# maze_hub_1_1.net
KiCad netlist of a schematic drawn in EAGLE
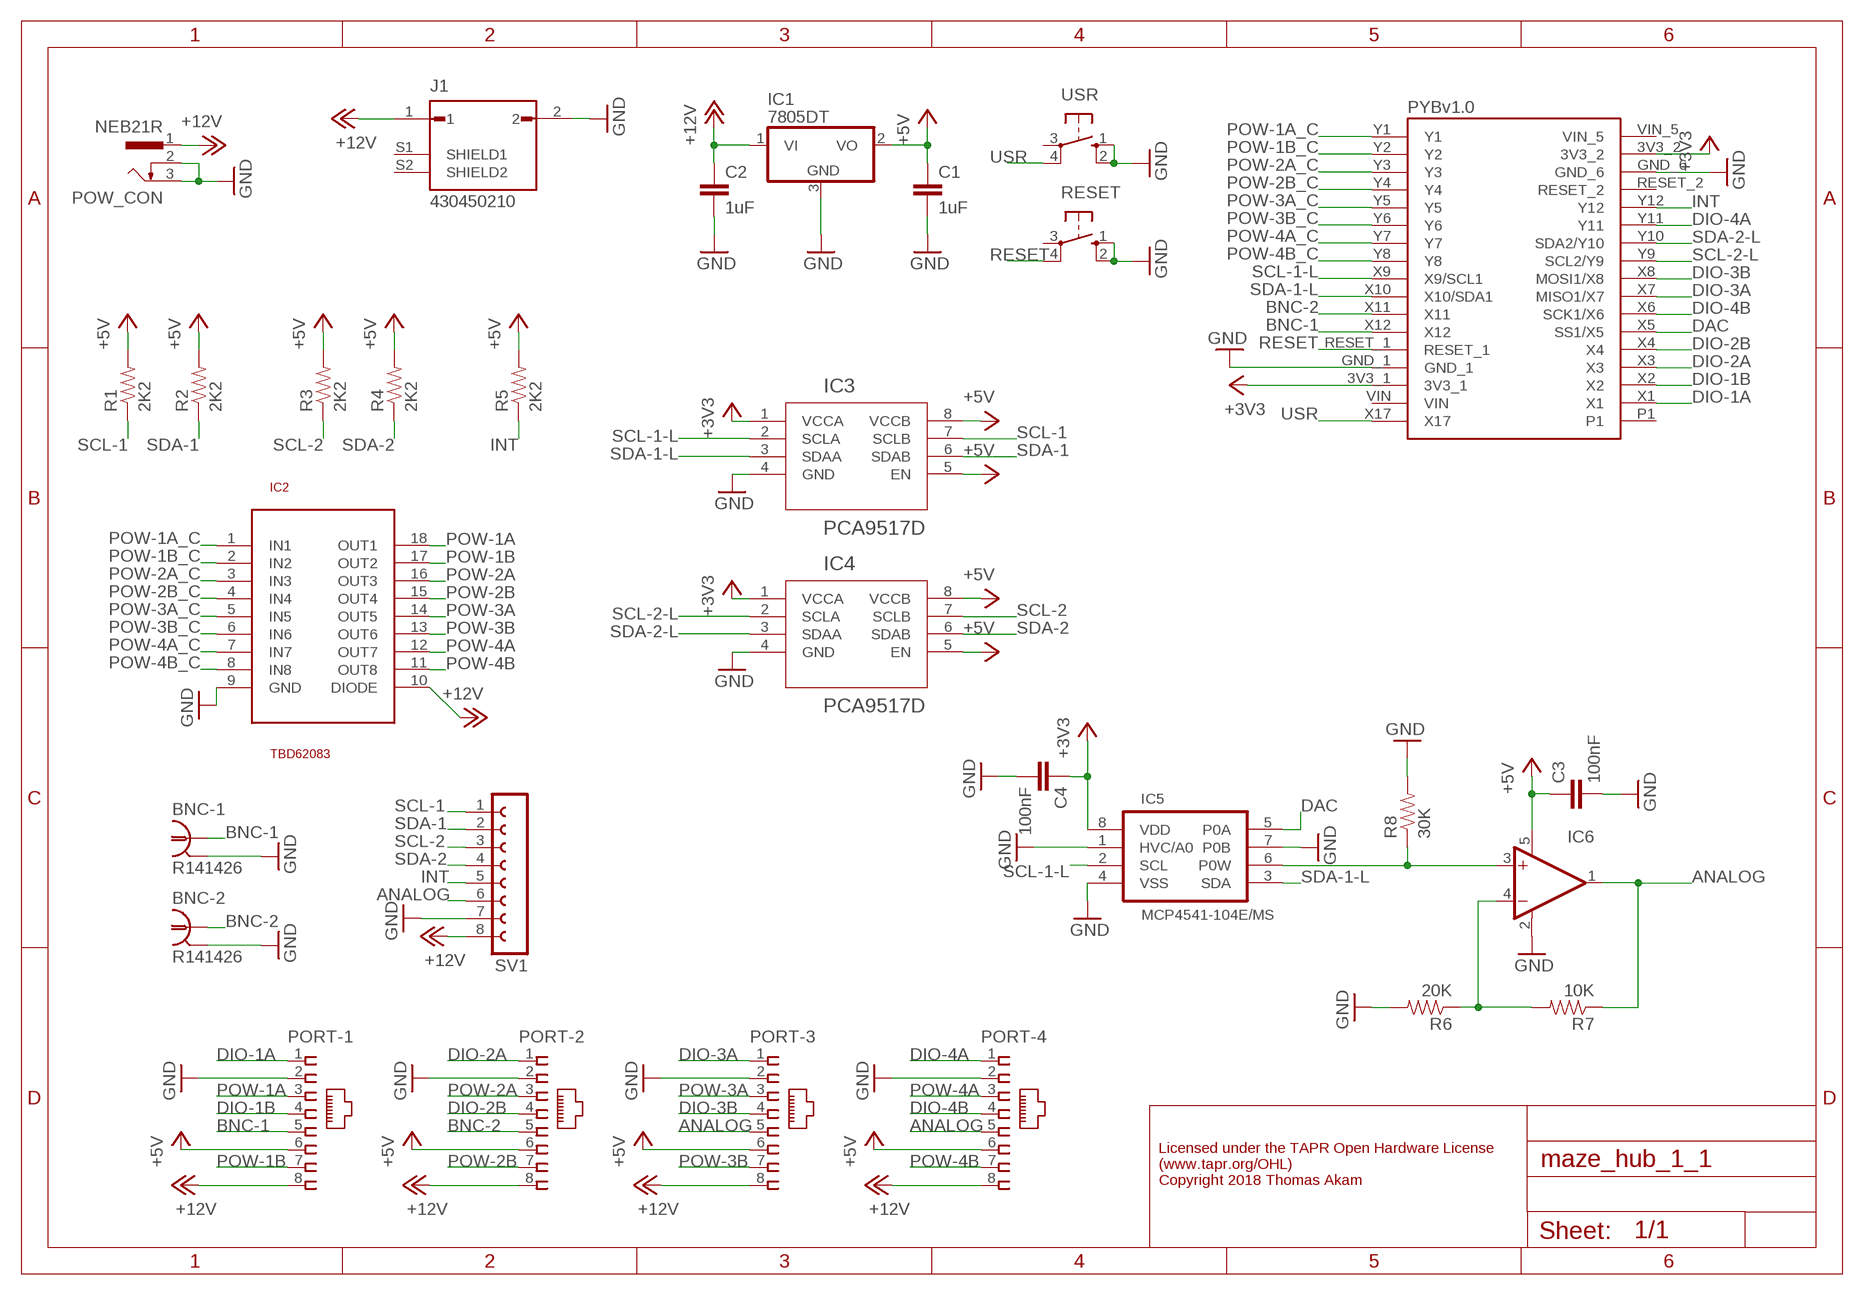
[diagram p0: schematic, sheet 1]

(export (version "E")
  (design (tool "Eeschema 10.0.6"))
  (components
    (comp (ref "BNC-1")
      (value "R141426")
      (footprint "eagle-import:R141426")
      (fields (field (name "MF") "FARNELL") (field (name "MPN") "R141426161"))
      (libsource (lib "eagle-import") (part "R141426"))
    )
    (comp (ref "BNC-2")
      (value "R141426")
      (footprint "eagle-import:R141426")
      (fields (field (name "MF") "FARNELL") (field (name "MPN") "R141426161"))
      (libsource (lib "eagle-import") (part "R141426"))
    )
    (comp (ref "C1")
      (value "1uF")
      (footprint "eagle-import:C1206")
      (libsource (lib "eagle-import") (part "resistor_C-EUC1206"))
    )
    (comp (ref "C2")
      (value "1uF")
      (footprint "eagle-import:C1206")
      (libsource (lib "eagle-import") (part "resistor_C-EUC1206"))
    )
    (comp (ref "C3")
      (value "100nF")
      (footprint "eagle-import:C0805")
      (libsource (lib "eagle-import") (part "C-EUC0805"))
    )
    (comp (ref "C4")
      (value "100nF")
      (footprint "eagle-import:C0805")
      (libsource (lib "eagle-import") (part "C-EUC0805"))
    )
    (comp (ref "IC1")
      (value "7805DT")
      (footprint "eagle-import:TO252")
      (libsource (lib "eagle-import") (part "78DT05"))
    )
    (comp (ref "IC2")
      (value "TBD62083")
      (footprint "eagle-import:SO18L")
      (libsource (lib "eagle-import") (part "ULN2803"))
    )
    (comp (ref "IC3")
      (value "PCA9517D")
      (footprint "eagle-import:D8")
      (libsource (lib "eagle-import") (part "PCA9517D"))
    )
    (comp (ref "IC4")
      (value "PCA9517D")
      (footprint "eagle-import:D8")
      (libsource (lib "eagle-import") (part "PCA9517D"))
    )
    (comp (ref "IC5")
      (value "MCP4541-104E/MS")
      (footprint "eagle-import:SOP65P490X110-8N")
      (libsource (lib "eagle-import") (part "MCP4541-104E/MS"))
    )
    (comp (ref "IC6")
      (value "OPA197")
      (footprint "eagle-import:SOT23-5")
      (libsource (lib "eagle-import") (part "OPA197"))
    )
    (comp (ref "J1")
      (value "430450210")
      (footprint "eagle-import:MOLEX_430450210")
      (fields (field (name "MF") "Molex") (field (name "MP") "43045-0210"))
      (libsource (lib "eagle-import") (part "430450210"))
    )
    (comp (ref "PORT-1")
      (value "RJ45VERTICAL")
      (footprint "eagle-import:RJ45-NO-SHIELD-VERTICAL")
      (libsource (lib "eagle-import") (part "RJ45VERTICAL"))
    )
    (comp (ref "PORT-2")
      (value "RJ45VERTICAL")
      (footprint "eagle-import:RJ45-NO-SHIELD-VERTICAL")
      (libsource (lib "eagle-import") (part "RJ45VERTICAL"))
    )
    (comp (ref "PORT-3")
      (value "RJ45VERTICAL")
      (footprint "eagle-import:RJ45-NO-SHIELD-VERTICAL")
      (libsource (lib "eagle-import") (part "RJ45VERTICAL"))
    )
    (comp (ref "PORT-4")
      (value "RJ45VERTICAL")
      (footprint "eagle-import:RJ45-NO-SHIELD-VERTICAL")
      (libsource (lib "eagle-import") (part "RJ45VERTICAL"))
    )
    (comp (ref "POW_CON")
      (value "NEB21R")
      (footprint "eagle-import:NEB21R")
      (fields (field (name "MPN") "NEB 21 R"))
      (libsource (lib "eagle-import") (part "NEB21R"))
    )
    (comp (ref "R1")
      (value "2K2")
      (footprint "eagle-import:0805")
      (libsource (lib "eagle-import") (part "0.3OHM-1/8W-1%(0805)"))
    )
    (comp (ref "R2")
      (value "2K2")
      (footprint "eagle-import:0805")
      (libsource (lib "eagle-import") (part "0.3OHM-1/8W-1%(0805)"))
    )
    (comp (ref "R3")
      (value "2K2")
      (footprint "eagle-import:0805")
      (libsource (lib "eagle-import") (part "0.3OHM-1/8W-1%(0805)"))
    )
    (comp (ref "R4")
      (value "2K2")
      (footprint "eagle-import:0805")
      (libsource (lib "eagle-import") (part "0.3OHM-1/8W-1%(0805)"))
    )
    (comp (ref "R5")
      (value "2K2")
      (footprint "eagle-import:0805")
      (libsource (lib "eagle-import") (part "0.3OHM-1/8W-1%(0805)"))
    )
    (comp (ref "R6")
      (value "20K")
      (footprint "eagle-import:0805")
      (libsource (lib "eagle-import") (part "0.3OHM-1/8W-1%(0805)"))
    )
    (comp (ref "R7")
      (value "10K")
      (footprint "eagle-import:0805")
      (libsource (lib "eagle-import") (part "0.3OHM-1/8W-1%(0805)"))
    )
    (comp (ref "R8")
      (value "30K")
      (footprint "eagle-import:0805")
      (libsource (lib "eagle-import") (part "0.3OHM-1/8W-1%(0805)"))
    )
    (comp (ref "RESET")
      (value "40-XX")
      (footprint "eagle-import:B3F-40XX")
      (fields
        (field (name "MF") "OMRON COMPONENTS USA")
        (field (name "MPN") "B3F-4000")
        (field (name "MF_1") "OMRON COMPONENTS USA")
        (field (name "MPN_1") "B3F-4000")
        (field (name "OC_FARNELL") "176434")
        (field (name "OC_NEWARK") "36K3105")
      )
      (libsource (lib "eagle-import") (part "40-XX"))
    )
    (comp (ref "SV1")
      (value "FE08W")
      (footprint "eagle-import:FE08W")
      (libsource (lib "eagle-import") (part "FE08W"))
    )
    (comp (ref "U$1")
      (value "PYBOARD-REDUCED")
      (footprint "eagle-import:PYBOARD-REDUCED")
      (libsource (lib "eagle-import") (part "PYBOARD-REDUCED"))
    )
    (comp (ref "USR")
      (value "40-XX")
      (footprint "eagle-import:B3F-40XX")
      (fields (field (name "MF") "OMRON COMPONENTS USA") (field (name "MPN") "B3F-4000"))
      (libsource (lib "eagle-import") (part "40-XX"))
    )
  )
  (nets
    (net (code "1") (name "+3V3") (class "Default")
      (node (ref "C4") (pin "1") (pinfunction "1_1") (pintype "passive"))
      (node (ref "IC3") (pin "1") (pinfunction "VCCA_1") (pintype "power_in"))
      (node (ref "IC4") (pin "1") (pinfunction "VCCA_1") (pintype "power_in"))
      (node (ref "IC5") (pin "8") (pinfunction "VDD_8") (pintype "power_in"))
      (node (ref "U$1") (pin "3V3_1") (pinfunction "3V3_1_3V3_1") (pintype "bidirectional"))
      (node (ref "U$1") (pin "3V3_2") (pinfunction "3V3_2_3V3_2") (pintype "bidirectional"))
    )
    (net (code "2") (name "+5V") (class "Default")
      (node (ref "C1") (pin "1") (pinfunction "1_1") (pintype "passive"))
      (node (ref "C3") (pin "1") (pinfunction "1_1") (pintype "passive"))
      (node (ref "IC1") (pin "2") (pinfunction "VO_2") (pintype "passive"))
      (node (ref "IC3") (pin "5") (pinfunction "EN_5") (pintype "passive"))
      (node (ref "IC3") (pin "8") (pinfunction "VCCB_8") (pintype "power_in"))
      (node (ref "IC4") (pin "5") (pinfunction "EN_5") (pintype "passive"))
      (node (ref "IC4") (pin "8") (pinfunction "VCCB_8") (pintype "power_in"))
      (node (ref "IC6") (pin "5") (pinfunction "V+_5") (pintype "power_in"))
      (node (ref "PORT-1") (pin "6") (pinfunction "6_6") (pintype "passive"))
      (node (ref "PORT-2") (pin "6") (pinfunction "6_6") (pintype "passive"))
      (node (ref "PORT-3") (pin "6") (pinfunction "6_6") (pintype "passive"))
      (node (ref "PORT-4") (pin "6") (pinfunction "6_6") (pintype "passive"))
      (node (ref "R1") (pin "2") (pinfunction "2_2") (pintype "passive"))
      (node (ref "R2") (pin "2") (pinfunction "2_2") (pintype "passive"))
      (node (ref "R3") (pin "2") (pinfunction "2_2") (pintype "passive"))
      (node (ref "R4") (pin "2") (pinfunction "2_2") (pintype "passive"))
      (node (ref "R5") (pin "2") (pinfunction "2_2") (pintype "passive"))
    )
    (net (code "3") (name "+12V") (class "Default")
      (node (ref "C2") (pin "1") (pinfunction "1_1") (pintype "passive"))
      (node (ref "IC1") (pin "1") (pinfunction "VI_1") (pintype "input"))
      (node (ref "IC2") (pin "10") (pinfunction "DIODE_10") (pintype "power_in"))
      (node (ref "J1") (pin "1") (pinfunction "1_1") (pintype "passive"))
      (node (ref "PORT-1") (pin "8") (pinfunction "8_8") (pintype "passive"))
      (node (ref "PORT-2") (pin "8") (pinfunction "8_8") (pintype "passive"))
      (node (ref "PORT-3") (pin "8") (pinfunction "8_8") (pintype "passive"))
      (node (ref "PORT-4") (pin "8") (pinfunction "8_8") (pintype "passive"))
      (node (ref "POW_CON") (pin "1") (pinfunction "1_1") (pintype "passive"))
      (node (ref "SV1") (pin "8") (pinfunction "8_8") (pintype "passive"))
    )
    (net (code "4") (name "/ANALOG") (class "Default")
      (node (ref "IC6") (pin "1") (pinfunction "OUT_1") (pintype "output"))
      (node (ref "PORT-3") (pin "5") (pinfunction "5_5") (pintype "passive"))
      (node (ref "PORT-4") (pin "5") (pinfunction "5_5") (pintype "passive"))
      (node (ref "R7") (pin "1") (pinfunction "1_1") (pintype "passive"))
      (node (ref "SV1") (pin "6") (pinfunction "6_6") (pintype "passive"))
    )
    (net (code "5") (name "/BNC-1") (class "Default")
      (node (ref "BNC-1") (pin "1") (pinfunction "1_1") (pintype "passive"))
      (node (ref "PORT-1") (pin "5") (pinfunction "5_5") (pintype "passive"))
      (node (ref "U$1") (pin "X12") (pinfunction "X12_X12") (pintype "bidirectional"))
    )
    (net (code "6") (name "/BNC-2") (class "Default")
      (node (ref "BNC-2") (pin "1") (pinfunction "1_1") (pintype "passive"))
      (node (ref "PORT-2") (pin "5") (pinfunction "5_5") (pintype "passive"))
      (node (ref "U$1") (pin "X11") (pinfunction "X11_X11") (pintype "bidirectional"))
    )
    (net (code "7") (name "/DAC") (class "Default")
      (node (ref "IC5") (pin "5") (pinfunction "P0A_5") (pintype "passive"))
      (node (ref "U$1") (pin "X5") (pinfunction "SS1/X5_X5") (pintype "bidirectional"))
    )
    (net (code "8") (name "/DIO-1A") (class "Default")
      (node (ref "PORT-1") (pin "1") (pinfunction "1_1") (pintype "passive"))
      (node (ref "U$1") (pin "X1") (pinfunction "X1_X1") (pintype "bidirectional"))
    )
    (net (code "9") (name "/DIO-1B") (class "Default")
      (node (ref "PORT-1") (pin "4") (pinfunction "4_4") (pintype "passive"))
      (node (ref "U$1") (pin "X2") (pinfunction "X2_X2") (pintype "bidirectional"))
    )
    (net (code "10") (name "/DIO-2A") (class "Default")
      (node (ref "PORT-2") (pin "1") (pinfunction "1_1") (pintype "passive"))
      (node (ref "U$1") (pin "X3") (pinfunction "X3_X3") (pintype "bidirectional"))
    )
    (net (code "11") (name "/DIO-2B") (class "Default")
      (node (ref "PORT-2") (pin "4") (pinfunction "4_4") (pintype "passive"))
      (node (ref "U$1") (pin "X4") (pinfunction "X4_X4") (pintype "bidirectional"))
    )
    (net (code "12") (name "/DIO-3A") (class "Default")
      (node (ref "PORT-3") (pin "1") (pinfunction "1_1") (pintype "passive"))
      (node (ref "U$1") (pin "X7") (pinfunction "MISO1/X7_X7") (pintype "bidirectional"))
    )
    (net (code "13") (name "/DIO-3B") (class "Default")
      (node (ref "PORT-3") (pin "4") (pinfunction "4_4") (pintype "passive"))
      (node (ref "U$1") (pin "X8") (pinfunction "MOSI1/X8_X8") (pintype "bidirectional"))
    )
    (net (code "14") (name "/DIO-4A") (class "Default")
      (node (ref "PORT-4") (pin "1") (pinfunction "1_1") (pintype "passive"))
      (node (ref "U$1") (pin "Y11") (pinfunction "Y11_Y11") (pintype "bidirectional"))
    )
    (net (code "15") (name "/DIO-4B") (class "Default")
      (node (ref "PORT-4") (pin "4") (pinfunction "4_4") (pintype "passive"))
      (node (ref "U$1") (pin "X6") (pinfunction "SCK1/X6_X6") (pintype "bidirectional"))
    )
    (net (code "16") (name "/INT") (class "Default")
      (node (ref "R5") (pin "1") (pinfunction "1_1") (pintype "passive"))
      (node (ref "SV1") (pin "5") (pinfunction "5_5") (pintype "passive"))
      (node (ref "U$1") (pin "Y12") (pinfunction "Y12_Y12") (pintype "bidirectional"))
    )
    (net (code "17") (name "/POW-1A") (class "Default")
      (node (ref "IC2") (pin "18") (pinfunction "OUT1_18") (pintype "open_collector"))
      (node (ref "PORT-1") (pin "3") (pinfunction "3_3") (pintype "passive"))
    )
    (net (code "18") (name "/POW-1A_C") (class "Default")
      (node (ref "IC2") (pin "1") (pinfunction "IN1_1") (pintype "input"))
      (node (ref "U$1") (pin "Y1") (pinfunction "Y1_Y1") (pintype "bidirectional"))
    )
    (net (code "19") (name "/POW-1B") (class "Default")
      (node (ref "IC2") (pin "17") (pinfunction "OUT2_17") (pintype "open_collector"))
      (node (ref "PORT-1") (pin "7") (pinfunction "7_7") (pintype "passive"))
    )
    (net (code "20") (name "/POW-1B_C") (class "Default")
      (node (ref "IC2") (pin "2") (pinfunction "IN2_2") (pintype "input"))
      (node (ref "U$1") (pin "Y2") (pinfunction "Y2_Y2") (pintype "bidirectional"))
    )
    (net (code "21") (name "/POW-2A") (class "Default")
      (node (ref "IC2") (pin "16") (pinfunction "OUT3_16") (pintype "open_collector"))
      (node (ref "PORT-2") (pin "3") (pinfunction "3_3") (pintype "passive"))
    )
    (net (code "22") (name "/POW-2A_C") (class "Default")
      (node (ref "IC2") (pin "3") (pinfunction "IN3_3") (pintype "input"))
      (node (ref "U$1") (pin "Y3") (pinfunction "Y3_Y3") (pintype "bidirectional"))
    )
    (net (code "23") (name "/POW-2B") (class "Default")
      (node (ref "IC2") (pin "15") (pinfunction "OUT4_15") (pintype "open_collector"))
      (node (ref "PORT-2") (pin "7") (pinfunction "7_7") (pintype "passive"))
    )
    (net (code "24") (name "/POW-2B_C") (class "Default")
      (node (ref "IC2") (pin "4") (pinfunction "IN4_4") (pintype "input"))
      (node (ref "U$1") (pin "Y4") (pinfunction "Y4_Y4") (pintype "bidirectional"))
    )
    (net (code "25") (name "/POW-3A") (class "Default")
      (node (ref "IC2") (pin "14") (pinfunction "OUT5_14") (pintype "open_collector"))
      (node (ref "PORT-3") (pin "3") (pinfunction "3_3") (pintype "passive"))
    )
    (net (code "26") (name "/POW-3A_C") (class "Default")
      (node (ref "IC2") (pin "5") (pinfunction "IN5_5") (pintype "input"))
      (node (ref "U$1") (pin "Y5") (pinfunction "Y5_Y5") (pintype "bidirectional"))
    )
    (net (code "27") (name "/POW-3B") (class "Default")
      (node (ref "IC2") (pin "13") (pinfunction "OUT6_13") (pintype "open_collector"))
      (node (ref "PORT-3") (pin "7") (pinfunction "7_7") (pintype "passive"))
    )
    (net (code "28") (name "/POW-3B_C") (class "Default")
      (node (ref "IC2") (pin "6") (pinfunction "IN6_6") (pintype "input"))
      (node (ref "U$1") (pin "Y6") (pinfunction "Y6_Y6") (pintype "bidirectional"))
    )
    (net (code "29") (name "/POW-4A") (class "Default")
      (node (ref "IC2") (pin "12") (pinfunction "OUT7_12") (pintype "open_collector"))
      (node (ref "PORT-4") (pin "3") (pinfunction "3_3") (pintype "passive"))
    )
    (net (code "30") (name "/POW-4A_C") (class "Default")
      (node (ref "IC2") (pin "7") (pinfunction "IN7_7") (pintype "input"))
      (node (ref "U$1") (pin "Y7") (pinfunction "Y7_Y7") (pintype "bidirectional"))
    )
    (net (code "31") (name "/POW-4B") (class "Default")
      (node (ref "IC2") (pin "11") (pinfunction "OUT8_11") (pintype "open_collector"))
      (node (ref "PORT-4") (pin "7") (pinfunction "7_7") (pintype "passive"))
    )
    (net (code "32") (name "/POW-4B_C") (class "Default")
      (node (ref "IC2") (pin "8") (pinfunction "IN8_8") (pintype "input"))
      (node (ref "U$1") (pin "Y8") (pinfunction "Y8_Y8") (pintype "bidirectional"))
    )
    (net (code "33") (name "/RESET") (class "Default")
      (node (ref "RESET") (pin "4") (pinfunction "P1_4") (pintype "passive"))
      (node (ref "U$1") (pin "RESET_1") (pinfunction "RESET_1_RESET_1") (pintype "bidirectional"))
    )
    (net (code "34") (name "/SCL-1") (class "Default")
      (node (ref "IC3") (pin "7") (pinfunction "SCLB_7") (pintype "passive"))
      (node (ref "R1") (pin "1") (pinfunction "1_1") (pintype "passive"))
      (node (ref "SV1") (pin "1") (pinfunction "1_1") (pintype "passive"))
    )
    (net (code "35") (name "/SCL-1-L") (class "Default")
      (node (ref "IC3") (pin "2") (pinfunction "SCLA_2") (pintype "passive"))
      (node (ref "IC5") (pin "2") (pinfunction "SCL_2") (pintype "input"))
      (node (ref "U$1") (pin "X9") (pinfunction "X9/SCL1_X9") (pintype "bidirectional"))
    )
    (net (code "36") (name "/SCL-2") (class "Default")
      (node (ref "IC4") (pin "7") (pinfunction "SCLB_7") (pintype "passive"))
      (node (ref "R3") (pin "1") (pinfunction "1_1") (pintype "passive"))
      (node (ref "SV1") (pin "3") (pinfunction "3_3") (pintype "passive"))
    )
    (net (code "37") (name "/SCL-2-L") (class "Default")
      (node (ref "IC4") (pin "2") (pinfunction "SCLA_2") (pintype "passive"))
      (node (ref "U$1") (pin "Y9") (pinfunction "SCL2/Y9_Y9") (pintype "bidirectional"))
    )
    (net (code "38") (name "/SDA-1") (class "Default")
      (node (ref "IC3") (pin "6") (pinfunction "SDAB_6") (pintype "passive"))
      (node (ref "R2") (pin "1") (pinfunction "1_1") (pintype "passive"))
      (node (ref "SV1") (pin "2") (pinfunction "2_2") (pintype "passive"))
    )
    (net (code "39") (name "/SDA-1-L") (class "Default")
      (node (ref "IC3") (pin "3") (pinfunction "SDAA_3") (pintype "passive"))
      (node (ref "IC5") (pin "3") (pinfunction "SDA_3") (pintype "bidirectional"))
      (node (ref "U$1") (pin "X10") (pinfunction "X10/SDA1_X10") (pintype "bidirectional"))
    )
    (net (code "40") (name "/SDA-2") (class "Default")
      (node (ref "IC4") (pin "6") (pinfunction "SDAB_6") (pintype "passive"))
      (node (ref "R4") (pin "1") (pinfunction "1_1") (pintype "passive"))
      (node (ref "SV1") (pin "4") (pinfunction "4_4") (pintype "passive"))
    )
    (net (code "41") (name "/SDA-2-L") (class "Default")
      (node (ref "IC4") (pin "3") (pinfunction "SDAA_3") (pintype "passive"))
      (node (ref "U$1") (pin "Y10") (pinfunction "SDA2/Y10_Y10") (pintype "bidirectional"))
    )
    (net (code "42") (name "/USR") (class "Default")
      (node (ref "U$1") (pin "X17") (pinfunction "X17_X17") (pintype "bidirectional"))
      (node (ref "USR") (pin "4") (pinfunction "P1_4") (pintype "passive"))
    )
    (net (code "43") (name "GND") (class "Default")
      (node (ref "BNC-1") (pin "2") (pinfunction "GND_2") (pintype "power_in"))
      (node (ref "BNC-2") (pin "2") (pinfunction "GND_2") (pintype "power_in"))
      (node (ref "C1") (pin "2") (pinfunction "2_2") (pintype "passive"))
      (node (ref "C2") (pin "2") (pinfunction "2_2") (pintype "passive"))
      (node (ref "C3") (pin "2") (pinfunction "2_2") (pintype "passive"))
      (node (ref "C4") (pin "2") (pinfunction "2_2") (pintype "passive"))
      (node (ref "IC1") (pin "3") (pinfunction "GND_3") (pintype "passive"))
      (node (ref "IC2") (pin "9") (pinfunction "GND_9") (pintype "power_in"))
      (node (ref "IC3") (pin "4") (pinfunction "GND_4") (pintype "power_in"))
      (node (ref "IC4") (pin "4") (pinfunction "GND_4") (pintype "power_in"))
      (node (ref "IC5") (pin "1") (pinfunction "HVC/A0_1") (pintype "input"))
      (node (ref "IC5") (pin "4") (pinfunction "VSS_4") (pintype "power_in"))
      (node (ref "IC5") (pin "7") (pinfunction "P0B_7") (pintype "passive"))
      (node (ref "IC6") (pin "2") (pinfunction "V-_2") (pintype "power_in"))
      (node (ref "J1") (pin "2") (pinfunction "2_2") (pintype "passive"))
      (node (ref "PORT-1") (pin "2") (pinfunction "2_2") (pintype "passive"))
      (node (ref "PORT-2") (pin "2") (pinfunction "2_2") (pintype "passive"))
      (node (ref "PORT-3") (pin "2") (pinfunction "2_2") (pintype "passive"))
      (node (ref "PORT-4") (pin "2") (pinfunction "2_2") (pintype "passive"))
      (node (ref "POW_CON") (pin "2") (pinfunction "2_2") (pintype "passive"))
      (node (ref "POW_CON") (pin "3") (pinfunction "3_3") (pintype "passive"))
      (node (ref "R6") (pin "2") (pinfunction "2_2") (pintype "passive"))
      (node (ref "R8") (pin "2") (pinfunction "2_2") (pintype "passive"))
      (node (ref "RESET") (pin "1") (pinfunction "S_1") (pintype "passive"))
      (node (ref "RESET") (pin "2") (pinfunction "S1_2") (pintype "passive"))
      (node (ref "SV1") (pin "7") (pinfunction "7_7") (pintype "passive"))
      (node (ref "U$1") (pin "GND_1") (pinfunction "GND_1_GND_1") (pintype "bidirectional"))
      (node (ref "U$1") (pin "GND_6") (pinfunction "GND_6_GND_6") (pintype "bidirectional"))
      (node (ref "USR") (pin "1") (pinfunction "S_1") (pintype "passive"))
      (node (ref "USR") (pin "2") (pinfunction "S1_2") (pintype "passive"))
    )
    (net (code "44") (name "Net-(IC5-P0W)") (class "Default")
      (node (ref "IC5") (pin "6") (pinfunction "P0W_6") (pintype "passive"))
      (node (ref "IC6") (pin "3") (pinfunction "+IN_3") (pintype "input"))
      (node (ref "R8") (pin "1") (pinfunction "1_1") (pintype "passive"))
    )
    (net (code "45") (name "Net-(IC6--IN)") (class "Default")
      (node (ref "IC6") (pin "4") (pinfunction "-IN_4") (pintype "input"))
      (node (ref "R6") (pin "1") (pinfunction "1_1") (pintype "passive"))
      (node (ref "R7") (pin "2") (pinfunction "2_2") (pintype "passive"))
    )
    (net (code "46") (name "unconnected-(J1-SHIELD1-PadS1)") (class "Default")
      (node (ref "J1") (pin "S1") (pinfunction "SHIELD1_S1") (pintype "passive"))
    )
    (net (code "47") (name "unconnected-(J1-SHIELD2-PadS2)") (class "Default")
      (node (ref "J1") (pin "S2") (pinfunction "SHIELD2_S2") (pintype "passive"))
    )
    (net (code "48") (name "unconnected-(RESET-P-Pad3)") (class "Default")
      (node (ref "RESET") (pin "3") (pinfunction "P_3") (pintype "passive"))
    )
    (net (code "49") (name "unconnected-(U$1-PadP1)") (class "Default")
      (node (ref "U$1") (pin "P1") (pinfunction "P1_P1") (pintype "bidirectional"))
    )
    (net (code "50") (name "unconnected-(U$1-PadRESET_2)") (class "Default")
      (node (ref "U$1") (pin "RESET_2") (pinfunction "RESET_2_RESET_2") (pintype "bidirectional"))
    )
    (net (code "51") (name "unconnected-(U$1-PadVIN)") (class "Default")
      (node (ref "U$1") (pin "VIN") (pinfunction "VIN_VIN") (pintype "bidirectional"))
    )
    (net (code "52") (name "unconnected-(U$1-PadVIN_5)") (class "Default")
      (node (ref "U$1") (pin "VIN_5") (pinfunction "VIN_5_VIN_5") (pintype "bidirectional"))
    )
    (net (code "53") (name "unconnected-(USR-P-Pad3)") (class "Default")
      (node (ref "USR") (pin "3") (pinfunction "P_3") (pintype "passive"))
    )
  )
)
